# Simple-Transmitter-2SC9014.net
KiCad netlist of a schematic drawn in EAGLE
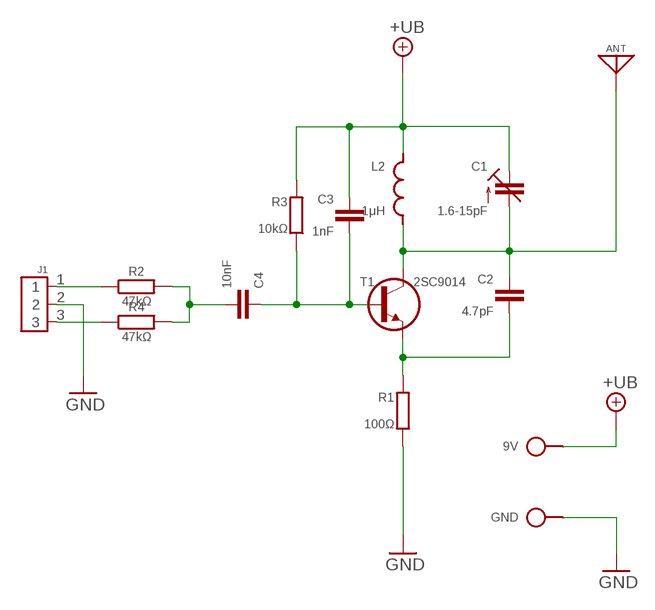
[diagram p0: schematic, sheet 1]

(export (version "E")
  (design (tool "Eeschema 10.0.6"))
  (components
    (comp (ref "9V")
      (value "SPAD")
      (footprint "eagle-import:SPAD")
      (libsource (lib "eagle-import") (part "SPAD"))
    )
    (comp (ref "ANT")
      (value "ANT")
      (footprint "eagle-import:SPAD")
      (libsource (lib "eagle-import") (part "ANT"))
    )
    (comp (ref "C1")
      (value "1.6-15pF")
      (footprint "eagle-import:TRIM-2222-808")
      (libsource (lib "eagle-import") (part "C-TR-PH201272222-808-2PINB"))
    )
    (comp (ref "C2")
      (value "4.7pF")
      (footprint "eagle-import:C025-015X024")
      (libsource (lib "eagle-import") (part "C025-015X024"))
    )
    (comp (ref "C3")
      (value "1nF")
      (footprint "eagle-import:C025-015X024")
      (libsource (lib "eagle-import") (part "C025-015X024"))
    )
    (comp (ref "C4")
      (value "10nF")
      (footprint "eagle-import:C050-020X036_V")
      (libsource (lib "eagle-import") (part "C050-020X036/V"))
    )
    (comp (ref "GND")
      (value "SPAD")
      (footprint "eagle-import:SPAD")
      (libsource (lib "eagle-import") (part "SPAD"))
    )
    (comp (ref "J1")
      (value "CONN-3P-3P")
      (footprint "eagle-import:CONN-3P")
      (libsource (lib "eagle-import") (part "CONN-3P-3P"))
    )
    (comp (ref "L2")
      (value "1μH")
      (footprint "eagle-import:L-04_7")
      (libsource (lib "eagle-import") (part "L-SHORT04/7"))
    )
    (comp (ref "R1")
      (value "100Ω")
      (footprint "eagle-import:0204_2V")
      (libsource (lib "eagle-import") (part "R0204/2V"))
    )
    (comp (ref "R2")
      (value "47kΩ")
      (footprint "eagle-import:0204_10-V")
      (libsource (lib "eagle-import") (part "R-H0204/10-V"))
    )
    (comp (ref "R3")
      (value "10kΩ")
      (footprint "eagle-import:0204_10-V")
      (libsource (lib "eagle-import") (part "R0204/10-V"))
    )
    (comp (ref "R4")
      (value "47kΩ")
      (footprint "eagle-import:0204_10-V")
      (libsource (lib "eagle-import") (part "R-H0204/10-V"))
    )
    (comp (ref "T1")
      (value "2SC9014")
      (footprint "eagle-import:TO92-EBC")
      (libsource (lib "eagle-import") (part "2SC9014"))
    )
  )
  (nets
    (net (code "1") (name "+UB") (class "Default")
      (node (ref "9V") (pin "1") (pinfunction "P$1_1") (pintype "bidirectional"))
      (node (ref "C1") (pin "3") (pinfunction "E_3") (pintype "passive"))
      (node (ref "C3") (pin "1") (pinfunction "1_1") (pintype "passive"))
      (node (ref "L2") (pin "2") (pinfunction "2_2") (pintype "passive"))
      (node (ref "R3") (pin "1") (pinfunction "1_1") (pintype "passive"))
    )
    (net (code "2") (name "GND") (class "Default")
      (node (ref "GND") (pin "1") (pinfunction "P$1_1") (pintype "bidirectional"))
      (node (ref "J1") (pin "2") (pinfunction "2_2") (pintype "bidirectional"))
      (node (ref "R1") (pin "1") (pinfunction "2_1") (pintype "passive"))
    )
    (net (code "3") (name "Net-(C1-A)") (class "Default")
      (node (ref "ANT") (pin "1") (pinfunction "1_1") (pintype "output"))
      (node (ref "C1") (pin "2") (pinfunction "A_2") (pintype "passive"))
      (node (ref "C2") (pin "1") (pinfunction "1_1") (pintype "passive"))
      (node (ref "L2") (pin "1") (pinfunction "1_1") (pintype "passive"))
      (node (ref "T1") (pin "C") (pinfunction "C_C") (pintype "passive"))
    )
    (net (code "4") (name "Net-(C3-Pad2)") (class "Default")
      (node (ref "C3") (pin "2") (pinfunction "2_2") (pintype "passive"))
      (node (ref "C4") (pin "1") (pinfunction "1_1") (pintype "passive"))
      (node (ref "R3") (pin "2") (pinfunction "2_2") (pintype "passive"))
      (node (ref "T1") (pin "B") (pinfunction "B_B") (pintype "passive"))
    )
    (net (code "5") (name "Net-(C4-Pad2)") (class "Default")
      (node (ref "C4") (pin "2") (pinfunction "2_2") (pintype "passive"))
      (node (ref "R2") (pin "2") (pinfunction "2_2") (pintype "passive"))
      (node (ref "R4") (pin "2") (pinfunction "2_2") (pintype "passive"))
    )
    (net (code "6") (name "Net-(J1-Pad1)") (class "Default")
      (node (ref "J1") (pin "1") (pinfunction "1_1") (pintype "bidirectional"))
      (node (ref "R2") (pin "1") (pinfunction "1_1") (pintype "passive"))
    )
    (net (code "7") (name "Net-(J1-Pad3)") (class "Default")
      (node (ref "J1") (pin "3") (pinfunction "3_3") (pintype "bidirectional"))
      (node (ref "R4") (pin "1") (pinfunction "1_1") (pintype "passive"))
    )
    (net (code "8") (name "Net-(R1-1)") (class "Default")
      (node (ref "C2") (pin "2") (pinfunction "2_2") (pintype "passive"))
      (node (ref "R1") (pin "2") (pinfunction "1_2") (pintype "passive"))
      (node (ref "T1") (pin "E") (pinfunction "E_E") (pintype "passive"))
    )
  )
)
